# SparkFun_dToF-TMF8821.net
KiCad netlist of a schematic drawn in EAGLE
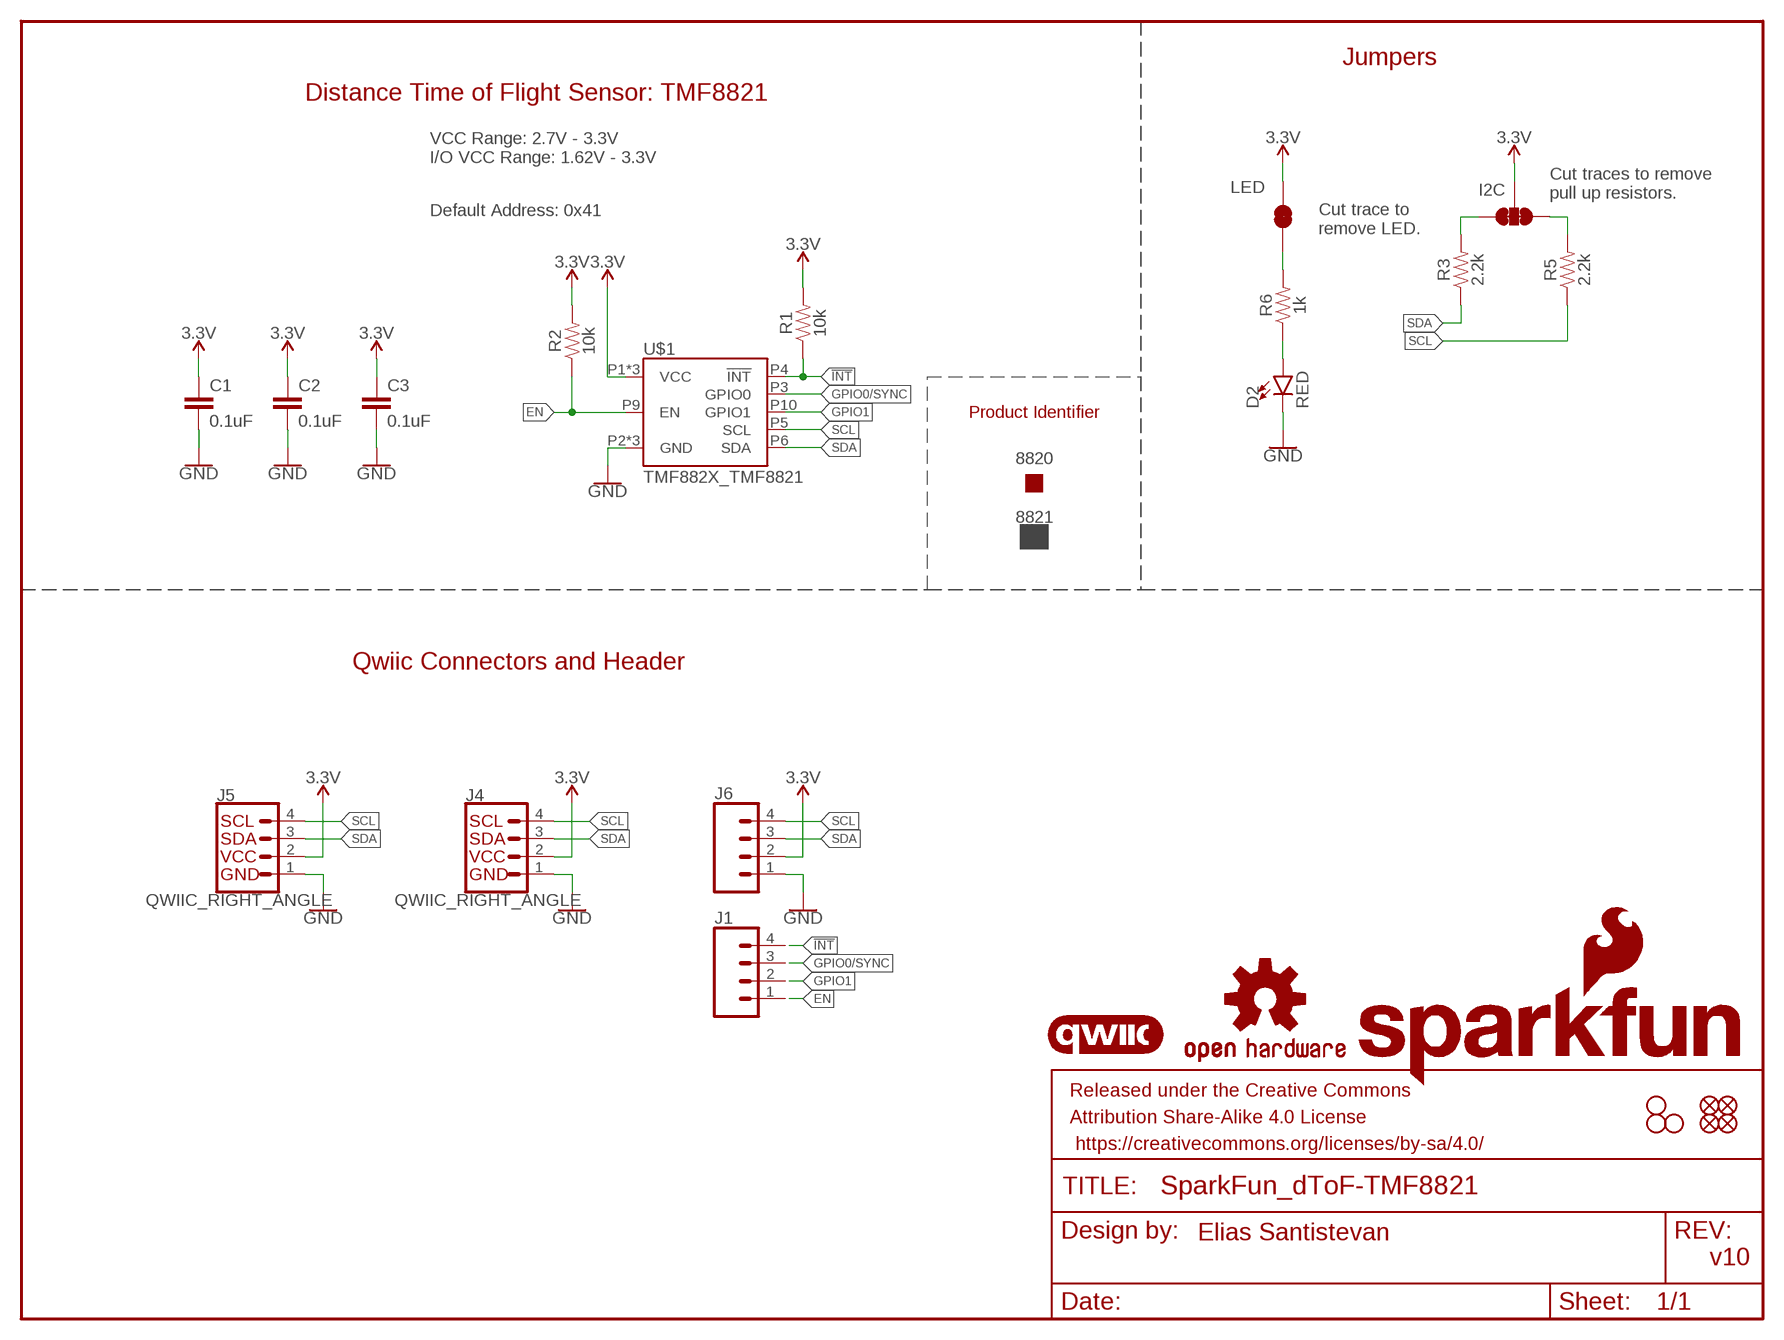
[diagram p0: schematic, sheet 1]

(export (version "E")
  (design (tool "Eeschema 10.0.6"))
  (components
    (comp (ref "8820")
      (value "PROD_ID_NO-PASTE_SILK")
      (footprint "eagle-import:PRODUCT_IDENT_NO_SILK")
      (libsource (lib "eagle-import") (part "PROD_ID_NO-PASTE_SILK"))
    )
    (comp (ref "8821")
      (value "PROD_ID_PASTE_SILK")
      (footprint "eagle-import:PRODUCT_IDENT_PASTE_SILK")
      (libsource (lib "eagle-import") (part "PROD_ID_PASTE_SILK"))
    )
    (comp (ref "C1")
      (value "0.1uF")
      (footprint "eagle-import:0402-TIGHT")
      (libsource (lib "eagle-import") (part "0.1UF-0402T-6.3V-10%-X7R"))
    )
    (comp (ref "C2")
      (value "0.1uF")
      (footprint "eagle-import:0402-TIGHT")
      (libsource (lib "eagle-import") (part "0.1UF-0402T-6.3V-10%-X7R"))
    )
    (comp (ref "C3")
      (value "0.1uF")
      (footprint "eagle-import:0402-TIGHT")
      (libsource (lib "eagle-import") (part "0.1UF-0402T-6.3V-10%-X7R"))
    )
    (comp (ref "D2")
      (value "RED")
      (footprint "eagle-import:LED-0603")
      (libsource (lib "eagle-import") (part "LED-RED0603"))
    )
    (comp (ref "FD5")
      (value "FIDUCIALUFIDUCIAL")
      (footprint "eagle-import:FIDUCIAL-MICRO")
      (libsource (lib "eagle-import") (part "FIDUCIALUFIDUCIAL"))
    )
    (comp (ref "FD6")
      (value "FIDUCIALUFIDUCIAL")
      (footprint "eagle-import:FIDUCIAL-MICRO")
      (libsource (lib "eagle-import") (part "FIDUCIALUFIDUCIAL"))
    )
    (comp (ref "FD7")
      (value "FIDUCIALUFIDUCIAL")
      (footprint "eagle-import:FIDUCIAL-MICRO")
      (libsource (lib "eagle-import") (part "FIDUCIALUFIDUCIAL"))
    )
    (comp (ref "FD8")
      (value "FIDUCIALUFIDUCIAL")
      (footprint "eagle-import:FIDUCIAL-MICRO")
      (libsource (lib "eagle-import") (part "FIDUCIALUFIDUCIAL"))
    )
    (comp (ref "FRAME2")
      (value "FRAME-LETTER")
      (footprint "eagle-import:CREATIVE_COMMONS")
      (libsource (lib "eagle-import") (part "FRAME-LETTER"))
    )
    (comp (ref "H5")
      (value "STAND-OFFTIGHT")
      (footprint "eagle-import:STAND-OFF-TIGHT")
      (libsource (lib "eagle-import") (part "STAND-OFFTIGHT"))
    )
    (comp (ref "H6")
      (value "STAND-OFFTIGHT")
      (footprint "eagle-import:STAND-OFF-TIGHT")
      (libsource (lib "eagle-import") (part "STAND-OFFTIGHT"))
    )
    (comp (ref "H8")
      (value "STAND-OFFTIGHT")
      (footprint "eagle-import:STAND-OFF-TIGHT")
      (libsource (lib "eagle-import") (part "STAND-OFFTIGHT"))
    )
    (comp (ref "I2C")
      (value "I2C_PU")
      (footprint "eagle-import:SMT-JUMPER_3_2-NC_TRACE_SILK")
      (libsource (lib "eagle-import") (part "JUMPER-SMT_3_2-NC_TRACE_SILK"))
    )
    (comp (ref "J1")
      (value "CONN_041X04_NO_SILK_NO_POP")
      (footprint "eagle-import:1X04_NO_SILK")
      (libsource (lib "eagle-import") (part "CONN_041X04_NO_SILK_NO_POP"))
    )
    (comp (ref "J4")
      (value "QWIIC_RIGHT_ANGLE")
      (footprint "eagle-import:JST04_1MM_RA")
      (libsource (lib "eagle-import") (part "QWIIC_CONNECTORJS-1MM"))
    )
    (comp (ref "J5")
      (value "QWIIC_RIGHT_ANGLE")
      (footprint "eagle-import:JST04_1MM_RA")
      (libsource (lib "eagle-import") (part "QWIIC_CONNECTORJS-1MM"))
    )
    (comp (ref "J6")
      (value "CONN_041X04_NO_SILK")
      (footprint "eagle-import:1X04_NO_SILK")
      (libsource (lib "eagle-import") (part "CONN_041X04_NO_SILK"))
    )
    (comp (ref "LED")
      (value "LED")
      (footprint "eagle-import:SMT-JUMPER_2_NC_TRACE_SILK")
      (libsource (lib "eagle-import") (part "JUMPER-SMT_2_NC_TRACE_SILK"))
    )
    (comp (ref "LOGO3")
      (value "SFE_LOGO_NAME_FLAME.1_INCH")
      (footprint "eagle-import:SFE_LOGO_NAME_FLAME_.1")
      (libsource (lib "eagle-import") (part "SFE_LOGO_NAME_FLAME.1_INCH"))
    )
    (comp (ref "LOGO4")
      (value "OSHW-LOGOS")
      (footprint "eagle-import:OSHW-LOGO-S")
      (libsource (lib "eagle-import") (part "OSHW-LOGOS"))
    )
    (comp (ref "R1")
      (value "10k")
      (footprint "eagle-import:0603")
      (libsource (lib "eagle-import") (part "10KOHM-0603-1/10W-1%"))
    )
    (comp (ref "R2")
      (value "10k")
      (footprint "eagle-import:0603")
      (libsource (lib "eagle-import") (part "10KOHM-0603-1/10W-1%"))
    )
    (comp (ref "R3")
      (value "2.2k")
      (footprint "eagle-import:0603")
      (libsource (lib "eagle-import") (part "2.2KOHM-0603-1/10W-1%"))
    )
    (comp (ref "R5")
      (value "2.2k")
      (footprint "eagle-import:0603")
      (libsource (lib "eagle-import") (part "2.2KOHM-0603-1/10W-1%"))
    )
    (comp (ref "R6")
      (value "1k")
      (footprint "eagle-import:0603")
      (libsource (lib "eagle-import") (part "1KOHM-0603-1/10W-1%"))
    )
    (comp (ref "U$1")
      (value "TMF882X_TMF8821")
      (footprint "eagle-import:TMF882X")
      (libsource (lib "eagle-import") (part "TMF882X_TMF8821"))
    )
    (comp (ref "U$6")
      (value "QWIIC_LOGO_5MM")
      (footprint "eagle-import:QWIIC_5MM")
      (libsource (lib "eagle-import") (part "QWIIC_LOGO_5MM"))
    )
  )
  (nets
    (net (code "1") (name "/~{INT}") (class "Default")
      (node (ref "J1") (pin "4") (pinfunction "4_4") (pintype "passive"))
      (node (ref "R1") (pin "1") (pinfunction "1_1") (pintype "passive"))
      (node (ref "U$1") (pin "P4") (pinfunction "~{INT}_P4") (pintype "bidirectional"))
    )
    (net (code "2") (name "3.3V") (class "Default")
      (node (ref "C1") (pin "1") (pinfunction "1_1") (pintype "passive"))
      (node (ref "C2") (pin "1") (pinfunction "1_1") (pintype "passive"))
      (node (ref "C3") (pin "1") (pinfunction "1_1") (pintype "passive"))
      (node (ref "I2C") (pin "2") (pinfunction "2_2") (pintype "passive"))
      (node (ref "J4") (pin "2") (pinfunction "2_2") (pintype "power_in"))
      (node (ref "J5") (pin "2") (pinfunction "2_2") (pintype "power_in"))
      (node (ref "J6") (pin "2") (pinfunction "2_2") (pintype "passive"))
      (node (ref "LED") (pin "2") (pinfunction "2_2") (pintype "passive"))
      (node (ref "R1") (pin "2") (pinfunction "2_2") (pintype "passive"))
      (node (ref "R2") (pin "2") (pinfunction "2_2") (pintype "passive"))
      (node (ref "U$1") (pin "P1") (pinfunction "VCC_P1") (pintype "power_in"))
      (node (ref "U$1") (pin "P12") (pinfunction "VCC_P12") (pintype "power_in"))
      (node (ref "U$1") (pin "P7") (pinfunction "VCC_P7") (pintype "power_in"))
    )
    (net (code "3") (name "EN") (class "Default")
      (node (ref "J1") (pin "1") (pinfunction "1_1") (pintype "passive"))
      (node (ref "R2") (pin "1") (pinfunction "1_1") (pintype "passive"))
      (node (ref "U$1") (pin "P9") (pinfunction "EN_P9") (pintype "input"))
    )
    (net (code "4") (name "GND") (class "Default")
      (node (ref "C1") (pin "2") (pinfunction "2_2") (pintype "passive"))
      (node (ref "C2") (pin "2") (pinfunction "2_2") (pintype "passive"))
      (node (ref "C3") (pin "2") (pinfunction "2_2") (pintype "passive"))
      (node (ref "D2") (pin "C") (pinfunction "C_C") (pintype "passive"))
      (node (ref "J4") (pin "1") (pinfunction "1_1") (pintype "power_in"))
      (node (ref "J5") (pin "1") (pinfunction "1_1") (pintype "power_in"))
      (node (ref "J6") (pin "1") (pinfunction "1_1") (pintype "passive"))
      (node (ref "U$1") (pin "P11") (pinfunction "GND_P11") (pintype "power_in"))
      (node (ref "U$1") (pin "P2") (pinfunction "GND_P2") (pintype "power_in"))
      (node (ref "U$1") (pin "P8") (pinfunction "GND_P8") (pintype "power_in"))
    )
    (net (code "5") (name "GPIO0{slash}SYNC") (class "Default")
      (node (ref "J1") (pin "3") (pinfunction "3_3") (pintype "passive"))
      (node (ref "U$1") (pin "P3") (pinfunction "GPIO0_P3") (pintype "bidirectional"))
    )
    (net (code "6") (name "GPIO1") (class "Default")
      (node (ref "J1") (pin "2") (pinfunction "2_2") (pintype "passive"))
      (node (ref "U$1") (pin "P10") (pinfunction "GPIO1_P10") (pintype "bidirectional"))
    )
    (net (code "7") (name "Net-(D2-PadA)") (class "Default")
      (node (ref "D2") (pin "A") (pinfunction "A_A") (pintype "passive"))
      (node (ref "R6") (pin "1") (pinfunction "1_1") (pintype "passive"))
    )
    (net (code "8") (name "Net-(I2C-Pad1)") (class "Default")
      (node (ref "I2C") (pin "1") (pinfunction "1_1") (pintype "passive"))
      (node (ref "R5") (pin "2") (pinfunction "2_2") (pintype "passive"))
    )
    (net (code "9") (name "Net-(I2C-Pad3)") (class "Default")
      (node (ref "I2C") (pin "3") (pinfunction "3_3") (pintype "passive"))
      (node (ref "R3") (pin "2") (pinfunction "2_2") (pintype "passive"))
    )
    (net (code "10") (name "Net-(LED-Pad1)") (class "Default")
      (node (ref "LED") (pin "1") (pinfunction "1_1") (pintype "passive"))
      (node (ref "R6") (pin "2") (pinfunction "2_2") (pintype "passive"))
    )
    (net (code "11") (name "SCL") (class "Default")
      (node (ref "J4") (pin "4") (pinfunction "4_4") (pintype "passive"))
      (node (ref "J5") (pin "4") (pinfunction "4_4") (pintype "passive"))
      (node (ref "J6") (pin "4") (pinfunction "4_4") (pintype "passive"))
      (node (ref "R5") (pin "1") (pinfunction "1_1") (pintype "passive"))
      (node (ref "U$1") (pin "P5") (pinfunction "SCL_P5") (pintype "bidirectional"))
    )
    (net (code "12") (name "SDA") (class "Default")
      (node (ref "J4") (pin "3") (pinfunction "3_3") (pintype "passive"))
      (node (ref "J5") (pin "3") (pinfunction "3_3") (pintype "passive"))
      (node (ref "J6") (pin "3") (pinfunction "3_3") (pintype "passive"))
      (node (ref "R3") (pin "1") (pinfunction "1_1") (pintype "passive"))
      (node (ref "U$1") (pin "P6") (pinfunction "SDA_P6") (pintype "bidirectional"))
    )
  )
)
